# spw_iso.net
KiCad netlist of a schematic drawn in Altium Designer
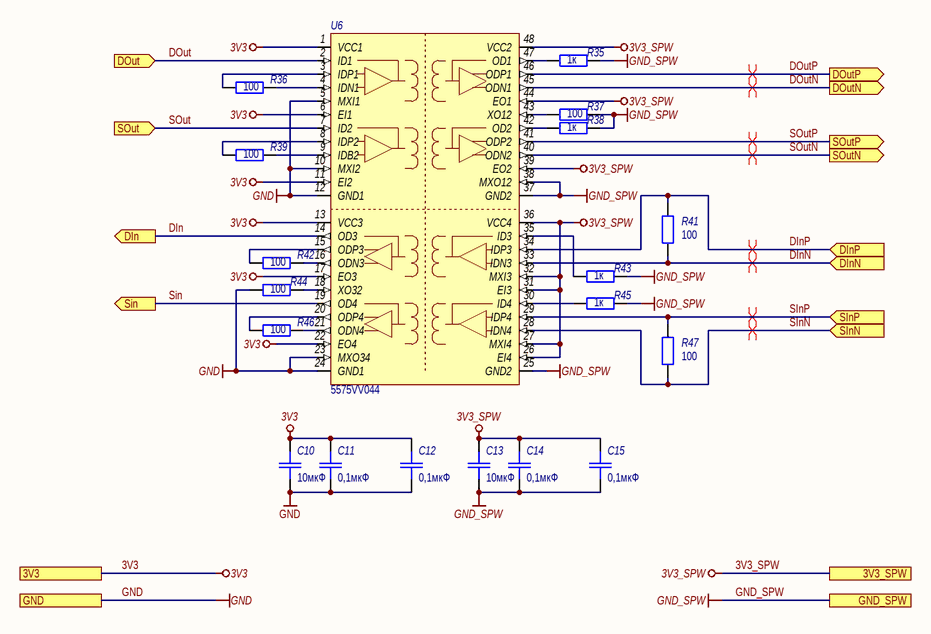
[diagram p0: spw_iso.SchDoc]

(export (version "E")
  (design (tool "Eeschema 10.0.6"))
  (components
    (comp (ref "C10")
      (value "10мкФ")
      (footprint "SMD_C0805")
      (description "Capacitor")
      (libsource (lib "Passive") (part "Capacitor"))
    )
    (comp (ref "C11")
      (value "0,1мкФ")
      (footprint "SMD_C0805")
      (description "Capacitor")
      (libsource (lib "Passive") (part "Capacitor"))
    )
    (comp (ref "C12")
      (value "0,1мкФ")
      (footprint "SMD_C0805")
      (description "Capacitor")
      (libsource (lib "Passive") (part "Capacitor"))
    )
    (comp (ref "C13")
      (value "10мкФ")
      (footprint "SMD_C0805")
      (description "Capacitor")
      (libsource (lib "Passive") (part "Capacitor"))
    )
    (comp (ref "C14")
      (value "0,1мкФ")
      (footprint "SMD_C0805")
      (description "Capacitor")
      (libsource (lib "Passive") (part "Capacitor"))
    )
    (comp (ref "C15")
      (value "0,1мкФ")
      (footprint "SMD_C0805")
      (description "Capacitor")
      (libsource (lib "Passive") (part "Capacitor"))
    )
    (comp (ref "R35")
      (value "1к")
      (footprint "SMD_0805")
      (description "Resistor")
      (libsource (lib "") (part "Resistor_1"))
    )
    (comp (ref "R36")
      (value "100")
      (footprint "SMD_0805")
      (description "Resistor")
      (libsource (lib "Passive") (part "Resistor"))
    )
    (comp (ref "R37")
      (value "100")
      (footprint "SMD_0805")
      (description "Resistor")
      (libsource (lib "") (part "Resistor_1"))
    )
    (comp (ref "R38")
      (value "1к")
      (footprint "SMD_0805")
      (description "Resistor")
      (libsource (lib "") (part "Resistor_1"))
    )
    (comp (ref "R39")
      (value "100")
      (footprint "SMD_0805")
      (description "Resistor")
      (libsource (lib "Passive") (part "Resistor"))
    )
    (comp (ref "R41")
      (value "100")
      (footprint "SMD_0805")
      (description "Resistor")
      (libsource (lib "") (part "Resistor_1"))
    )
    (comp (ref "R42")
      (value "100")
      (footprint "SMD_0805")
      (description "Resistor")
      (libsource (lib "Passive") (part "Resistor"))
    )
    (comp (ref "R43")
      (value "1к")
      (footprint "SMD_0805")
      (description "Resistor")
      (libsource (lib "") (part "Resistor_1"))
    )
    (comp (ref "R44")
      (value "100")
      (footprint "SMD_0805")
      (description "Resistor")
      (libsource (lib "Passive") (part "Resistor"))
    )
    (comp (ref "R45")
      (value "1к")
      (footprint "SMD_0805")
      (description "Resistor")
      (libsource (lib "") (part "Resistor_1"))
    )
    (comp (ref "R46")
      (value "100")
      (footprint "SMD_0805")
      (description "Resistor")
      (libsource (lib "Passive") (part "Resistor"))
    )
    (comp (ref "R47")
      (value "100")
      (footprint "SMD_0805")
      (description "Resistor")
      (libsource (lib "") (part "Resistor_1"))
    )
    (comp (ref "U6")
      (value "5575VV044")
      (footprint "MK 4159.48-1")
      (description "Микросхема гальванической развязки цифровых сигналов")
      (libsource (lib "5575BB044") (part "5575BB044"))
    )
  )
  (nets
    (net (code "1") (name "/DIn") (class "Default")
      (node (ref "U6") (pin "14") (pinfunction "OD3_14") (pintype "output"))
    )
    (net (code "2") (name "/DInN") (class "Default")
      (node (ref "R41") (pin "1") (pinfunction "1_1") (pintype "passive"))
      (node (ref "U6") (pin "33") (pinfunction "IDN3_33") (pintype "input"))
    )
    (net (code "3") (name "/DInP") (class "Default")
      (node (ref "R41") (pin "2") (pinfunction "2_2") (pintype "passive"))
      (node (ref "U6") (pin "34") (pinfunction "IDP3_34") (pintype "input"))
    )
    (net (code "4") (name "/DOut") (class "Default")
      (node (ref "U6") (pin "2") (pinfunction "ID1_2") (pintype "input"))
    )
    (net (code "5") (name "/DOutN") (class "Default")
      (node (ref "U6") (pin "45") (pinfunction "ODN1_45") (pintype "output"))
    )
    (net (code "6") (name "/DOutP") (class "Default")
      (node (ref "U6") (pin "46") (pinfunction "ODP1_46") (pintype "output"))
    )
    (net (code "7") (name "/SInN") (class "Default")
      (node (ref "R47") (pin "1") (pinfunction "1_1") (pintype "passive"))
      (node (ref "U6") (pin "28") (pinfunction "IDN4_28") (pintype "input"))
    )
    (net (code "8") (name "/SInP") (class "Default")
      (node (ref "R47") (pin "2") (pinfunction "2_2") (pintype "passive"))
      (node (ref "U6") (pin "29") (pinfunction "IDP4_29") (pintype "input"))
    )
    (net (code "9") (name "/SOut") (class "Default")
      (node (ref "U6") (pin "7") (pinfunction "ID2_7") (pintype "input"))
    )
    (net (code "10") (name "/SOutN") (class "Default")
      (node (ref "U6") (pin "40") (pinfunction "ODN2_40") (pintype "output"))
    )
    (net (code "11") (name "/SOutP") (class "Default")
      (node (ref "U6") (pin "41") (pinfunction "ODP2_41") (pintype "output"))
    )
    (net (code "12") (name "/Sin") (class "Default")
      (node (ref "U6") (pin "19") (pinfunction "OD4_19") (pintype "output"))
    )
    (net (code "13") (name "3V3") (class "Default")
      (node (ref "C10") (pin "2") (pinfunction "2_2") (pintype "passive"))
      (node (ref "C11") (pin "2") (pinfunction "2_2") (pintype "passive"))
      (node (ref "C12") (pin "2") (pinfunction "2_2") (pintype "passive"))
      (node (ref "U6") (pin "1") (pinfunction "VCC1_1") (pintype "power_in"))
      (node (ref "U6") (pin "11") (pinfunction "EI2_11") (pintype "input"))
      (node (ref "U6") (pin "13") (pinfunction "VCC3_13") (pintype "power_in"))
      (node (ref "U6") (pin "17") (pinfunction "EO3_17") (pintype "input"))
      (node (ref "U6") (pin "22") (pinfunction "EO4_22") (pintype "input"))
      (node (ref "U6") (pin "6") (pinfunction "EI1_6") (pintype "input"))
    )
    (net (code "14") (name "3V3_SPW") (class "Default")
      (node (ref "C13") (pin "2") (pinfunction "2_2") (pintype "passive"))
      (node (ref "C14") (pin "2") (pinfunction "2_2") (pintype "passive"))
      (node (ref "C15") (pin "2") (pinfunction "2_2") (pintype "passive"))
      (node (ref "U6") (pin "26") (pinfunction "EI4_26") (pintype "input"))
      (node (ref "U6") (pin "27") (pinfunction "MXI4_27") (pintype "input"))
      (node (ref "U6") (pin "31") (pinfunction "EI3_31") (pintype "input"))
      (node (ref "U6") (pin "32") (pinfunction "MXI3_32") (pintype "input"))
      (node (ref "U6") (pin "36") (pinfunction "VCC4_36") (pintype "power_in"))
      (node (ref "U6") (pin "39") (pinfunction "EO2_39") (pintype "input"))
      (node (ref "U6") (pin "44") (pinfunction "EO1_44") (pintype "input"))
      (node (ref "U6") (pin "48") (pinfunction "VCC2_48") (pintype "power_in"))
    )
    (net (code "15") (name "GND") (class "Default")
      (node (ref "C10") (pin "1") (pinfunction "1_1") (pintype "passive"))
      (node (ref "C11") (pin "1") (pinfunction "1_1") (pintype "passive"))
      (node (ref "C12") (pin "1") (pinfunction "1_1") (pintype "passive"))
      (node (ref "R44") (pin "2") (pinfunction "2_2") (pintype "passive"))
      (node (ref "U6") (pin "10") (pinfunction "MXI2_10") (pintype "input"))
      (node (ref "U6") (pin "12") (pinfunction "GND1_12") (pintype "power_in"))
      (node (ref "U6") (pin "23") (pinfunction "MXO34_23") (pintype "input"))
      (node (ref "U6") (pin "24") (pinfunction "GND1_24") (pintype "power_in"))
      (node (ref "U6") (pin "5") (pinfunction "MXI1_5") (pintype "input"))
    )
    (net (code "16") (name "GND_SPW") (class "Default")
      (node (ref "C13") (pin "1") (pinfunction "1_1") (pintype "passive"))
      (node (ref "C14") (pin "1") (pinfunction "1_1") (pintype "passive"))
      (node (ref "C15") (pin "1") (pinfunction "1_1") (pintype "passive"))
      (node (ref "R35") (pin "2") (pinfunction "2_2") (pintype "passive"))
      (node (ref "R37") (pin "2") (pinfunction "2_2") (pintype "passive"))
      (node (ref "R38") (pin "2") (pinfunction "2_2") (pintype "passive"))
      (node (ref "R43") (pin "2") (pinfunction "2_2") (pintype "passive"))
      (node (ref "R45") (pin "2") (pinfunction "2_2") (pintype "passive"))
      (node (ref "U6") (pin "25") (pinfunction "GND2_25") (pintype "power_in"))
      (node (ref "U6") (pin "37") (pinfunction "GND2_37") (pintype "power_in"))
      (node (ref "U6") (pin "38") (pinfunction "MXO12_38") (pintype "input"))
    )
    (net (code "17") (name "Net-(U6-ID3)") (class "Default")
      (node (ref "R43") (pin "1") (pinfunction "1_1") (pintype "passive"))
      (node (ref "U6") (pin "35") (pinfunction "ID3_35") (pintype "input"))
    )
    (net (code "18") (name "Net-(U6-ID4)") (class "Default")
      (node (ref "R45") (pin "1") (pinfunction "1_1") (pintype "passive"))
      (node (ref "U6") (pin "30") (pinfunction "ID4_30") (pintype "input"))
    )
    (net (code "19") (name "Net-(U6-IDB2)") (class "Default")
      (node (ref "R39") (pin "1") (pinfunction "1_1") (pintype "passive"))
      (node (ref "U6") (pin "9") (pinfunction "IDB2_9") (pintype "input"))
    )
    (net (code "20") (name "Net-(U6-IDN1)") (class "Default")
      (node (ref "R36") (pin "1") (pinfunction "1_1") (pintype "passive"))
      (node (ref "U6") (pin "4") (pinfunction "IDN1_4") (pintype "input"))
    )
    (net (code "21") (name "Net-(U6-IDP1)") (class "Default")
      (node (ref "R36") (pin "2") (pinfunction "2_2") (pintype "passive"))
      (node (ref "U6") (pin "3") (pinfunction "IDP1_3") (pintype "input"))
    )
    (net (code "22") (name "Net-(U6-IDP2)") (class "Default")
      (node (ref "R39") (pin "2") (pinfunction "2_2") (pintype "passive"))
      (node (ref "U6") (pin "8") (pinfunction "IDP2_8") (pintype "input"))
    )
    (net (code "23") (name "Net-(U6-OD1)") (class "Default")
      (node (ref "R35") (pin "1") (pinfunction "1_1") (pintype "passive"))
      (node (ref "U6") (pin "47") (pinfunction "OD1_47") (pintype "output"))
    )
    (net (code "24") (name "Net-(U6-OD2)") (class "Default")
      (node (ref "R38") (pin "1") (pinfunction "1_1") (pintype "passive"))
      (node (ref "U6") (pin "42") (pinfunction "OD2_42") (pintype "output"))
    )
    (net (code "25") (name "Net-(U6-ODN3)") (class "Default")
      (node (ref "R42") (pin "1") (pinfunction "1_1") (pintype "passive"))
      (node (ref "U6") (pin "16") (pinfunction "ODN3_16") (pintype "output"))
    )
    (net (code "26") (name "Net-(U6-ODN4)") (class "Default")
      (node (ref "R46") (pin "1") (pinfunction "1_1") (pintype "passive"))
      (node (ref "U6") (pin "21") (pinfunction "ODN4_21") (pintype "output"))
    )
    (net (code "27") (name "Net-(U6-ODP3)") (class "Default")
      (node (ref "R42") (pin "2") (pinfunction "2_2") (pintype "passive"))
      (node (ref "U6") (pin "15") (pinfunction "ODP3_15") (pintype "output"))
    )
    (net (code "28") (name "Net-(U6-ODP4)") (class "Default")
      (node (ref "R46") (pin "2") (pinfunction "2_2") (pintype "passive"))
      (node (ref "U6") (pin "20") (pinfunction "ODP4_20") (pintype "output"))
    )
    (net (code "29") (name "Net-(U6-XO12)") (class "Default")
      (node (ref "R37") (pin "1") (pinfunction "1_1") (pintype "passive"))
      (node (ref "U6") (pin "43") (pinfunction "XO12_43") (pintype "input"))
    )
    (net (code "30") (name "Net-(U6-XO32)") (class "Default")
      (node (ref "R44") (pin "1") (pinfunction "1_1") (pintype "passive"))
      (node (ref "U6") (pin "18") (pinfunction "XO32_18") (pintype "input"))
    )
  )
)
